# binaryclock.net
KiCad netlist of a schematic drawn in EAGLE
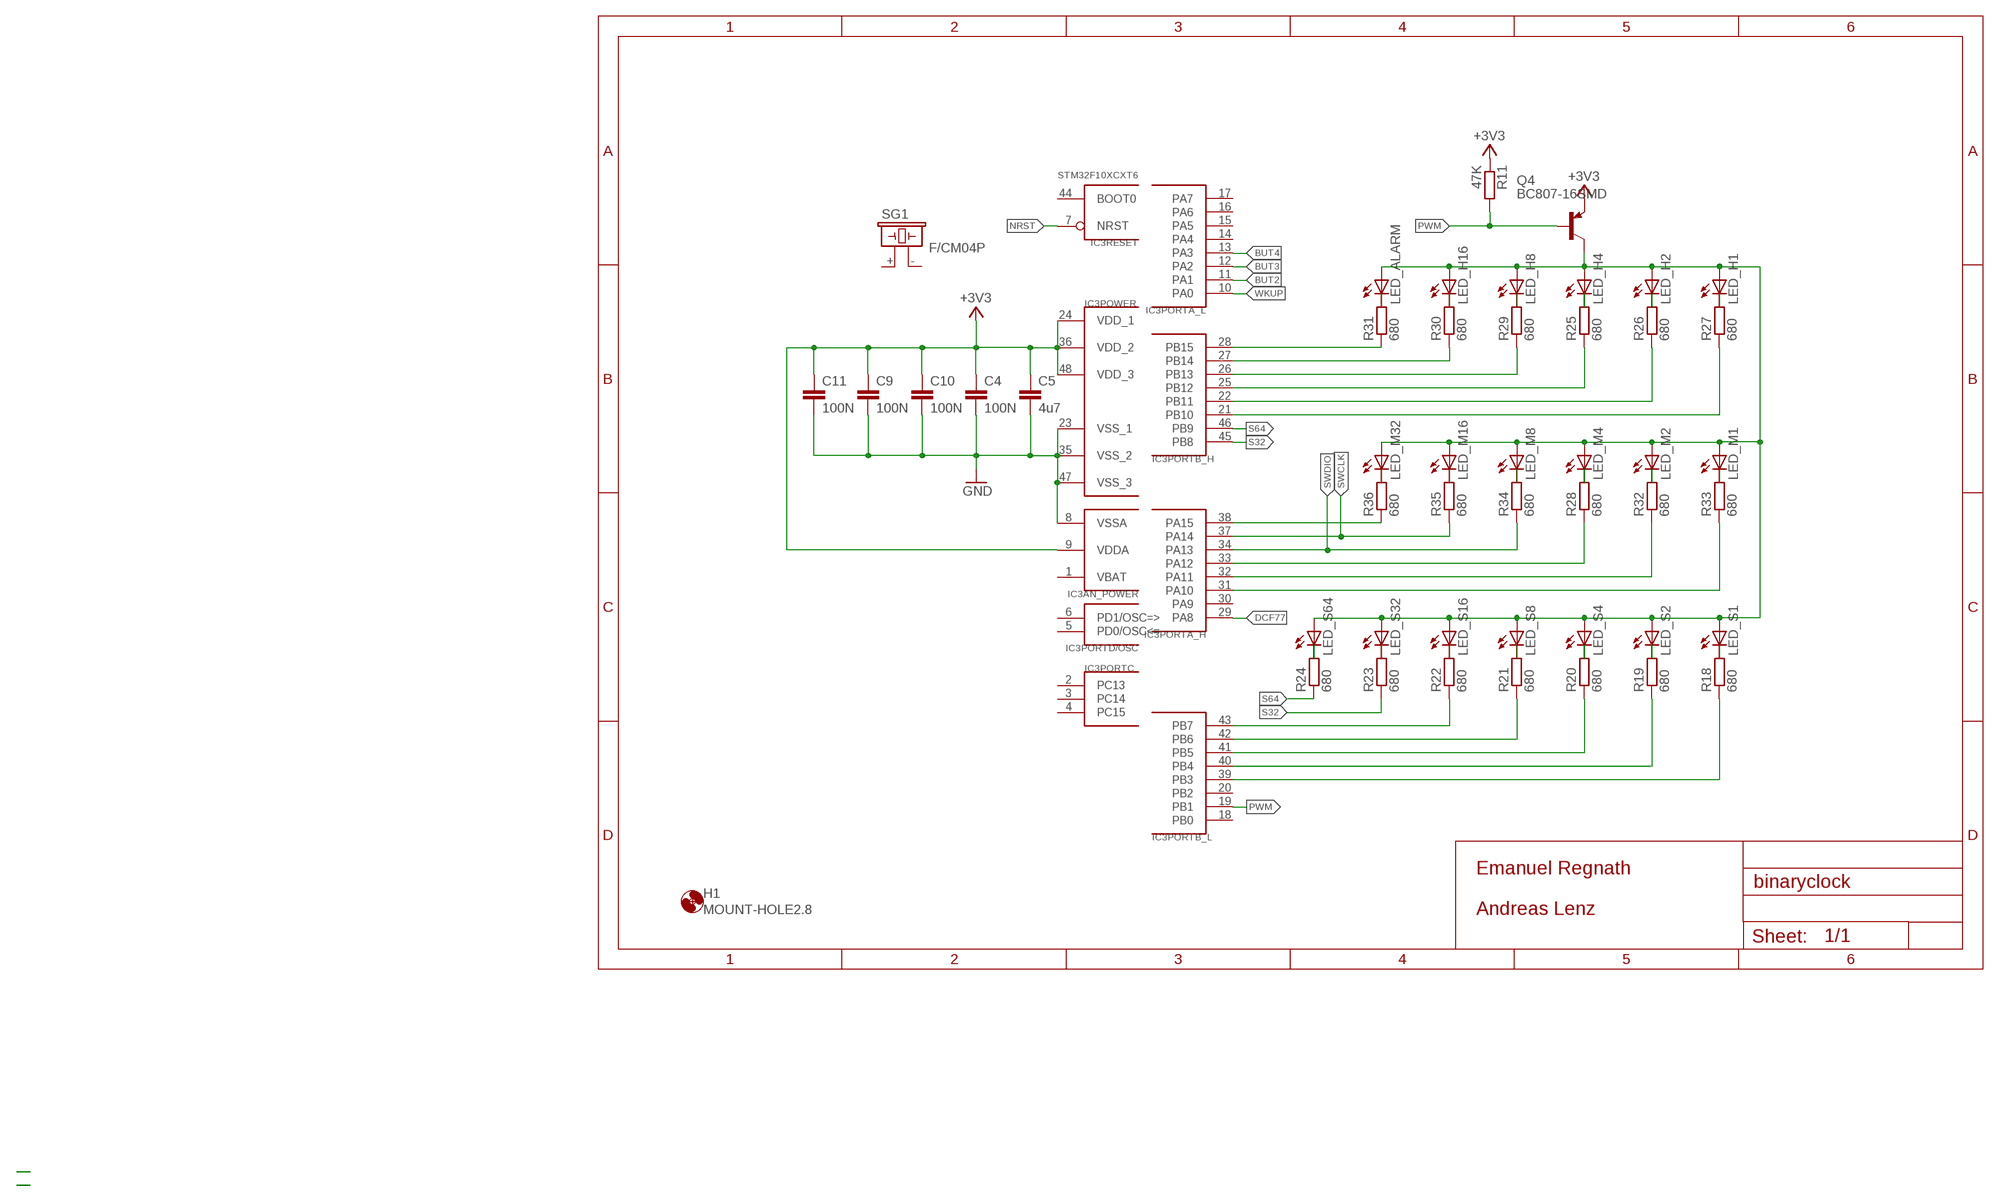
[diagram p0: schematic, sheet 1, part 1 of 2]
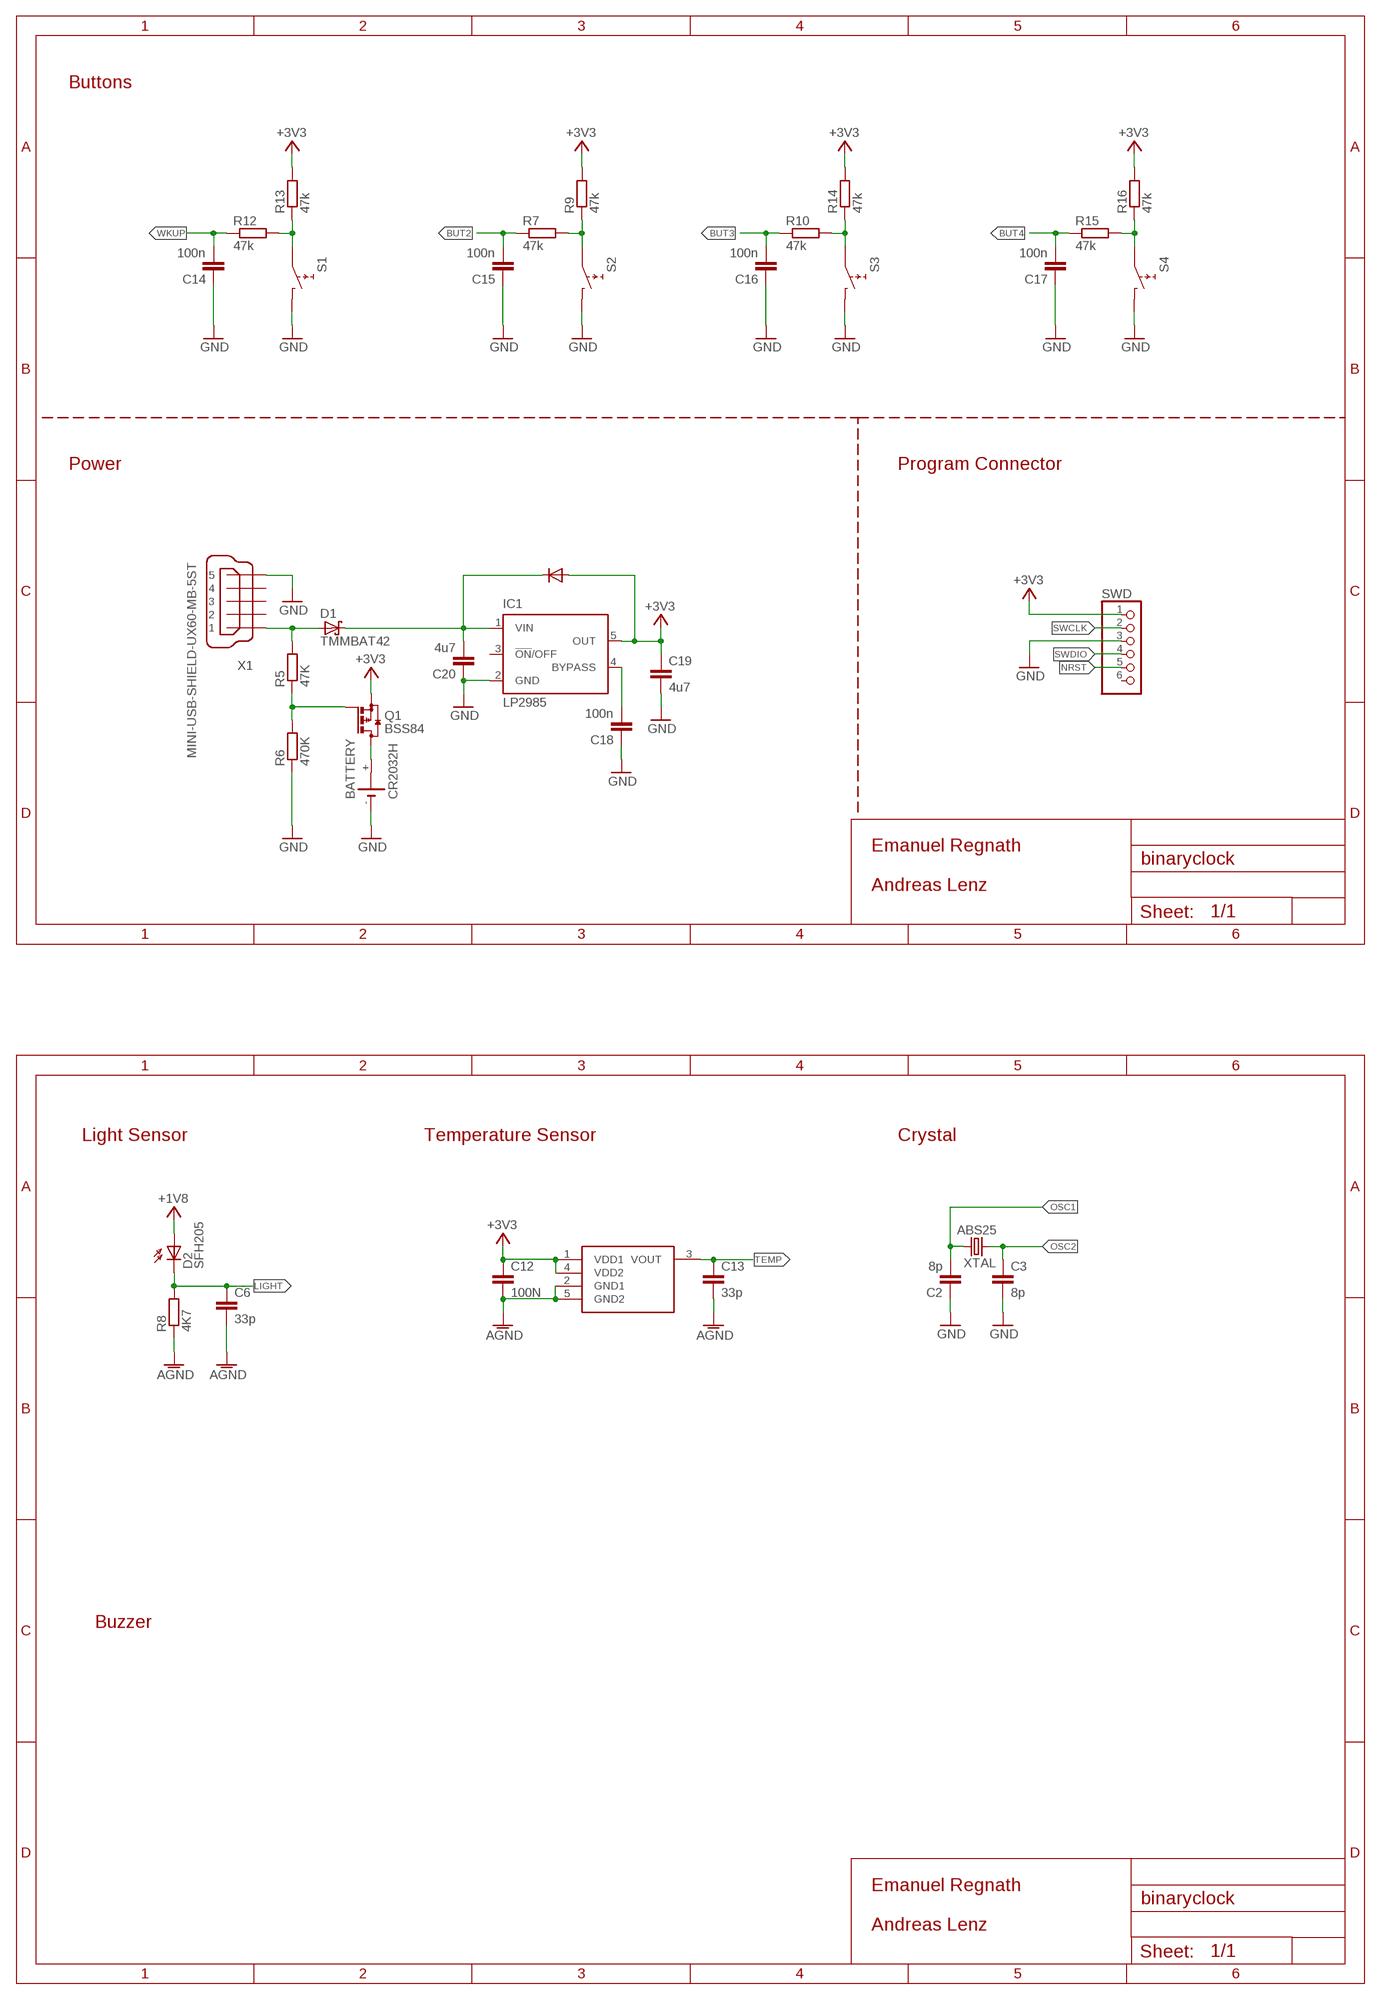
[diagram p1: schematic, sheet 1, part 2 of 2]

(export (version "E")
  (design (tool "Eeschema 10.0.6"))
  (components
    (comp (ref "BATTERY")
      (value "CR2032H")
      (footprint "eagle-import:CR2032H")
      (libsource (lib "eagle-import") (part "CR2032H"))
    )
    (comp (ref "BLA")
      (value "LMT85")
      (footprint "eagle-import:DCK_R-PDSO-G5")
      (libsource (lib "eagle-import") (part "LMT85"))
    )
    (comp (ref "C2")
      (value "8p")
      (footprint "eagle-import:C0805K")
      (libsource (lib "eagle-import") (part "C-EUC0805K"))
    )
    (comp (ref "C3")
      (value "8p")
      (footprint "eagle-import:C0805K")
      (libsource (lib "eagle-import") (part "C-EUC0805K"))
    )
    (comp (ref "C4")
      (value "100N")
      (footprint "eagle-import:C0603")
      (libsource (lib "eagle-import") (part "C-EUC0603"))
    )
    (comp (ref "C5")
      (value "4u7")
      (footprint "eagle-import:C0805")
      (libsource (lib "eagle-import") (part "C-EUC0805"))
    )
    (comp (ref "C6")
      (value "33p")
      (footprint "eagle-import:C0603")
      (libsource (lib "eagle-import") (part "C-EUC0603"))
    )
    (comp (ref "C9")
      (value "100N")
      (footprint "eagle-import:C0603")
      (libsource (lib "eagle-import") (part "C-EUC0603"))
    )
    (comp (ref "C10")
      (value "100N")
      (footprint "eagle-import:C0603")
      (libsource (lib "eagle-import") (part "C-EUC0603"))
    )
    (comp (ref "C11")
      (value "100N")
      (footprint "eagle-import:C0603")
      (libsource (lib "eagle-import") (part "C-EUC0603"))
    )
    (comp (ref "C12")
      (value "100N")
      (footprint "eagle-import:C0603")
      (libsource (lib "eagle-import") (part "C-EUC0603"))
    )
    (comp (ref "C13")
      (value "33p")
      (footprint "eagle-import:C0603")
      (libsource (lib "eagle-import") (part "C-EUC0603"))
    )
    (comp (ref "C14")
      (value "100n")
      (footprint "eagle-import:C0603K")
      (libsource (lib "eagle-import") (part "C-EUC0603K"))
    )
    (comp (ref "C15")
      (value "100n")
      (footprint "eagle-import:C0603K")
      (libsource (lib "eagle-import") (part "C-EUC0603K"))
    )
    (comp (ref "C16")
      (value "100n")
      (footprint "eagle-import:C0603K")
      (libsource (lib "eagle-import") (part "C-EUC0603K"))
    )
    (comp (ref "C17")
      (value "100n")
      (footprint "eagle-import:C0603K")
      (libsource (lib "eagle-import") (part "C-EUC0603K"))
    )
    (comp (ref "C18")
      (value "100n")
      (footprint "eagle-import:C0603K")
      (libsource (lib "eagle-import") (part "C-EUC0603K"))
    )
    (comp (ref "C19")
      (value "4u7")
      (footprint "eagle-import:C0805")
      (libsource (lib "eagle-import") (part "C-EUC0805"))
    )
    (comp (ref "C20")
      (value "4u7")
      (footprint "eagle-import:C0805")
      (libsource (lib "eagle-import") (part "C-EUC0805"))
    )
    (comp (ref "D1")
      (value "TMMBAT42")
      (footprint "eagle-import:SOD80")
      (libsource (lib "eagle-import") (part "TMMBAT42"))
    )
    (comp (ref "D2")
      (value "SFH205")
      (footprint "eagle-import:SFH205")
      (libsource (lib "eagle-import") (part "SFH205"))
    )
    (comp (ref "H1")
      (value "MOUNT-HOLE2.8")
      (footprint "eagle-import:2,8")
      (libsource (lib "eagle-import") (part "MOUNT-HOLE2.8"))
    )
    (comp (ref "IC1")
      (value "LP2985")
      (footprint "eagle-import:SOT23-5")
      (libsource (lib "eagle-import") (part "LP2985"))
    )
    (comp (ref "IC3")
      (value "STM32F10XCXT6")
      (footprint "eagle-import:TQFP48")
      (libsource (lib "eagle-import") (part "STM32F10XCXT6"))
    )
    (comp (ref "LED_ALARM")
      (value "LEDSML0603")
      (footprint "eagle-import:SML0603")
      (libsource (lib "eagle-import") (part "LEDSML0603"))
    )
    (comp (ref "LED_H1")
      (value "LEDSML0603")
      (footprint "eagle-import:SML0603")
      (libsource (lib "eagle-import") (part "LEDSML0603"))
    )
    (comp (ref "LED_H2")
      (value "LEDSML0603")
      (footprint "eagle-import:SML0603")
      (libsource (lib "eagle-import") (part "LEDSML0603"))
    )
    (comp (ref "LED_H4")
      (value "LEDSML0603")
      (footprint "eagle-import:SML0603")
      (libsource (lib "eagle-import") (part "LEDSML0603"))
    )
    (comp (ref "LED_H8")
      (value "LEDSML0603")
      (footprint "eagle-import:SML0603")
      (libsource (lib "eagle-import") (part "LEDSML0603"))
    )
    (comp (ref "LED_H16")
      (value "LEDSML0603")
      (footprint "eagle-import:SML0603")
      (libsource (lib "eagle-import") (part "LEDSML0603"))
    )
    (comp (ref "LED_M1")
      (value "LEDSML0603")
      (footprint "eagle-import:SML0603")
      (libsource (lib "eagle-import") (part "LEDSML0603"))
    )
    (comp (ref "LED_M2")
      (value "LEDSML0603")
      (footprint "eagle-import:SML0603")
      (libsource (lib "eagle-import") (part "LEDSML0603"))
    )
    (comp (ref "LED_M4")
      (value "LEDSML0603")
      (footprint "eagle-import:SML0603")
      (libsource (lib "eagle-import") (part "LEDSML0603"))
    )
    (comp (ref "LED_M8")
      (value "LEDSML0603")
      (footprint "eagle-import:SML0603")
      (libsource (lib "eagle-import") (part "LEDSML0603"))
    )
    (comp (ref "LED_M16")
      (value "LEDSML0603")
      (footprint "eagle-import:SML0603")
      (libsource (lib "eagle-import") (part "LEDSML0603"))
    )
    (comp (ref "LED_M32")
      (value "LEDSML0603")
      (footprint "eagle-import:SML0603")
      (libsource (lib "eagle-import") (part "LEDSML0603"))
    )
    (comp (ref "LED_S1")
      (value "LEDSML0603")
      (footprint "eagle-import:SML0603")
      (libsource (lib "eagle-import") (part "LEDSML0603"))
    )
    (comp (ref "LED_S2")
      (value "LEDSML0603")
      (footprint "eagle-import:SML0603")
      (libsource (lib "eagle-import") (part "LEDSML0603"))
    )
    (comp (ref "LED_S4")
      (value "LEDSML0603")
      (footprint "eagle-import:SML0603")
      (libsource (lib "eagle-import") (part "LEDSML0603"))
    )
    (comp (ref "LED_S8")
      (value "LEDSML0603")
      (footprint "eagle-import:SML0603")
      (libsource (lib "eagle-import") (part "LEDSML0603"))
    )
    (comp (ref "LED_S16")
      (value "LEDSML0603")
      (footprint "eagle-import:SML0603")
      (libsource (lib "eagle-import") (part "LEDSML0603"))
    )
    (comp (ref "LED_S32")
      (value "LEDSML0603")
      (footprint "eagle-import:SML0603")
      (libsource (lib "eagle-import") (part "LEDSML0603"))
    )
    (comp (ref "LED_S64")
      (value "LEDSML0603")
      (footprint "eagle-import:SML0603")
      (libsource (lib "eagle-import") (part "LEDSML0603"))
    )
    (comp (ref "Q1")
      (value "BSS84")
      (footprint "eagle-import:SOT23")
      (libsource (lib "eagle-import") (part "BSS84"))
    )
    (comp (ref "Q4")
      (value "BC807-16SMD")
      (footprint "eagle-import:SOT23-BEC")
      (libsource (lib "eagle-import") (part "BC807SMD-16"))
    )
    (comp (ref "R5")
      (value "47K")
      (footprint "eagle-import:R0805")
      (libsource (lib "eagle-import") (part "resistor_R-EU_R0805"))
    )
    (comp (ref "R6")
      (value "470K")
      (footprint "eagle-import:R0805")
      (libsource (lib "eagle-import") (part "resistor_R-EU_R0805"))
    )
    (comp (ref "R7")
      (value "47k")
      (footprint "eagle-import:M2012")
      (libsource (lib "eagle-import") (part "R-EU_M2012"))
    )
    (comp (ref "R8")
      (value "4K7")
      (footprint "eagle-import:R0603")
      (libsource (lib "eagle-import") (part "resistor_R-EU_R0603"))
    )
    (comp (ref "R9")
      (value "47k")
      (footprint "eagle-import:M2012")
      (libsource (lib "eagle-import") (part "R-EU_M2012"))
    )
    (comp (ref "R10")
      (value "47k")
      (footprint "eagle-import:M2012")
      (libsource (lib "eagle-import") (part "R-EU_M2012"))
    )
    (comp (ref "R11")
      (value "47K")
      (footprint "eagle-import:R0805")
      (libsource (lib "eagle-import") (part "resistor_R-EU_R0805"))
    )
    (comp (ref "R12")
      (value "47k")
      (footprint "eagle-import:M2012")
      (libsource (lib "eagle-import") (part "R-EU_M2012"))
    )
    (comp (ref "R13")
      (value "47k")
      (footprint "eagle-import:M2012")
      (libsource (lib "eagle-import") (part "R-EU_M2012"))
    )
    (comp (ref "R14")
      (value "47k")
      (footprint "eagle-import:M2012")
      (libsource (lib "eagle-import") (part "R-EU_M2012"))
    )
    (comp (ref "R15")
      (value "47k")
      (footprint "eagle-import:M2012")
      (libsource (lib "eagle-import") (part "R-EU_M2012"))
    )
    (comp (ref "R16")
      (value "47k")
      (footprint "eagle-import:M2012")
      (libsource (lib "eagle-import") (part "R-EU_M2012"))
    )
    (comp (ref "R18")
      (value "680")
      (footprint "eagle-import:R0603")
      (libsource (lib "eagle-import") (part "resistor_R-EU_R0603"))
    )
    (comp (ref "R19")
      (value "680")
      (footprint "eagle-import:R0603")
      (libsource (lib "eagle-import") (part "resistor_R-EU_R0603"))
    )
    (comp (ref "R20")
      (value "680")
      (footprint "eagle-import:R0603")
      (libsource (lib "eagle-import") (part "resistor_R-EU_R0603"))
    )
    (comp (ref "R21")
      (value "680")
      (footprint "eagle-import:R0603")
      (libsource (lib "eagle-import") (part "resistor_R-EU_R0603"))
    )
    (comp (ref "R22")
      (value "680")
      (footprint "eagle-import:R0603")
      (libsource (lib "eagle-import") (part "resistor_R-EU_R0603"))
    )
    (comp (ref "R23")
      (value "680")
      (footprint "eagle-import:R0603")
      (libsource (lib "eagle-import") (part "resistor_R-EU_R0603"))
    )
    (comp (ref "R24")
      (value "680")
      (footprint "eagle-import:R0603")
      (libsource (lib "eagle-import") (part "resistor_R-EU_R0603"))
    )
    (comp (ref "R25")
      (value "680")
      (footprint "eagle-import:R0603")
      (libsource (lib "eagle-import") (part "resistor_R-EU_R0603"))
    )
    (comp (ref "R26")
      (value "680")
      (footprint "eagle-import:R0603")
      (libsource (lib "eagle-import") (part "resistor_R-EU_R0603"))
    )
    (comp (ref "R27")
      (value "680")
      (footprint "eagle-import:R0603")
      (libsource (lib "eagle-import") (part "resistor_R-EU_R0603"))
    )
    (comp (ref "R28")
      (value "680")
      (footprint "eagle-import:R0603")
      (libsource (lib "eagle-import") (part "resistor_R-EU_R0603"))
    )
    (comp (ref "R29")
      (value "680")
      (footprint "eagle-import:R0603")
      (libsource (lib "eagle-import") (part "resistor_R-EU_R0603"))
    )
    (comp (ref "R30")
      (value "680")
      (footprint "eagle-import:R0603")
      (libsource (lib "eagle-import") (part "resistor_R-EU_R0603"))
    )
    (comp (ref "R31")
      (value "680")
      (footprint "eagle-import:R0603")
      (libsource (lib "eagle-import") (part "resistor_R-EU_R0603"))
    )
    (comp (ref "R32")
      (value "680")
      (footprint "eagle-import:R0603")
      (libsource (lib "eagle-import") (part "resistor_R-EU_R0603"))
    )
    (comp (ref "R33")
      (value "680")
      (footprint "eagle-import:R0603")
      (libsource (lib "eagle-import") (part "resistor_R-EU_R0603"))
    )
    (comp (ref "R34")
      (value "680")
      (footprint "eagle-import:R0603")
      (libsource (lib "eagle-import") (part "resistor_R-EU_R0603"))
    )
    (comp (ref "R35")
      (value "680")
      (footprint "eagle-import:R0603")
      (libsource (lib "eagle-import") (part "resistor_R-EU_R0603"))
    )
    (comp (ref "R36")
      (value "680")
      (footprint "eagle-import:R0603")
      (libsource (lib "eagle-import") (part "resistor_R-EU_R0603"))
    )
    (comp (ref "S1")
      (value "SWITCH1")
      (footprint "eagle-import:SWITCH1")
      (libsource (lib "eagle-import") (part "SWITCH1"))
    )
    (comp (ref "S2")
      (value "SWITCH1")
      (footprint "eagle-import:SWITCH1")
      (libsource (lib "eagle-import") (part "SWITCH1"))
    )
    (comp (ref "S3")
      (value "SWITCH1")
      (footprint "eagle-import:SWITCH1")
      (libsource (lib "eagle-import") (part "SWITCH1"))
    )
    (comp (ref "S4")
      (value "SWITCH1")
      (footprint "eagle-import:SWITCH1")
      (libsource (lib "eagle-import") (part "SWITCH1"))
    )
    (comp (ref "SG1")
      (value "F/CM04P")
      (footprint "eagle-import:F_CM04P")
      (libsource (lib "eagle-import") (part "F/CM04P"))
    )
    (comp (ref "SWD")
      (value "PINHD-1X6")
      (footprint "eagle-import:1X06")
      (libsource (lib "eagle-import") (part "PINHD-1X6"))
    )
    (comp (ref "X1")
      (value "MINI-USB-SHIELD-UX60-MB-5ST")
      (footprint "eagle-import:UX60-MB-5ST")
      (libsource (lib "eagle-import") (part "MINI-USB-SHIELD-UX60-MB-5ST"))
    )
    (comp (ref "XTAL")
      (value "ABS25")
      (footprint "eagle-import:ABS25")
      (fields (field (name "MPN") "MC-306 60.0KHZ  100PPM ,12.5PF"))
      (libsource (lib "eagle-import") (part "ABS25"))
    )
  )
  (nets
    (net (code "1") (name "+1V8") (class "Default")
      (node (ref "D2") (pin "A") (pinfunction "A_A") (pintype "passive"))
    )
    (net (code "2") (name "+3V3") (class "Default")
      (node (ref "BLA") (pin "1") (pinfunction "VDD1_1") (pintype "power_in"))
      (node (ref "BLA") (pin "4") (pinfunction "VDD2_4") (pintype "power_in"))
      (node (ref "C10") (pin "1") (pinfunction "1_1") (pintype "passive"))
      (node (ref "C11") (pin "1") (pinfunction "1_1") (pintype "passive"))
      (node (ref "C12") (pin "1") (pinfunction "1_1") (pintype "passive"))
      (node (ref "C19") (pin "1") (pinfunction "1_1") (pintype "passive"))
      (node (ref "C4") (pin "1") (pinfunction "1_1") (pintype "passive"))
      (node (ref "C5") (pin "1") (pinfunction "1_1") (pintype "passive"))
      (node (ref "C9") (pin "1") (pinfunction "1_1") (pintype "passive"))
      (node (ref "IC1") (pin "5") (pinfunction "OUT_5") (pintype "output"))
      (node (ref "IC3") (pin "24") (pinfunction "VDD_1_24") (pintype "power_in"))
      (node (ref "IC3") (pin "36") (pinfunction "VDD_2_36") (pintype "power_in"))
      (node (ref "IC3") (pin "48") (pinfunction "VDD_3_48") (pintype "power_in"))
      (node (ref "IC3") (pin "9") (pinfunction "VDDA_9") (pintype "power_in"))
      (node (ref "Q1") (pin "2") (pinfunction "S_2") (pintype "passive"))
      (node (ref "Q4") (pin "E") (pinfunction "E_E") (pintype "passive"))
      (node (ref "R11") (pin "1") (pinfunction "1_1") (pintype "passive"))
      (node (ref "R13") (pin "2") (pinfunction "2_2") (pintype "passive"))
      (node (ref "R14") (pin "2") (pinfunction "2_2") (pintype "passive"))
      (node (ref "R16") (pin "2") (pinfunction "2_2") (pintype "passive"))
      (node (ref "R9") (pin "2") (pinfunction "2_2") (pintype "passive"))
      (node (ref "SWD") (pin "1") (pinfunction "1_1") (pintype "passive"))
    )
    (net (code "3") (name "/VBAT") (class "Default")
      (node (ref "IC3") (pin "1") (pinfunction "VBAT_1") (pintype "power_in"))
    )
    (net (code "4") (name "AGND") (class "Default")
      (node (ref "BLA") (pin "2") (pinfunction "GND1_2") (pintype "power_in"))
      (node (ref "BLA") (pin "5") (pinfunction "GND2_5") (pintype "power_in"))
      (node (ref "C12") (pin "2") (pinfunction "2_2") (pintype "passive"))
      (node (ref "C13") (pin "2") (pinfunction "2_2") (pintype "passive"))
      (node (ref "C6") (pin "2") (pinfunction "2_2") (pintype "passive"))
      (node (ref "R8") (pin "1") (pinfunction "1_1") (pintype "passive"))
    )
    (net (code "5") (name "BUT2") (class "Default")
      (node (ref "C15") (pin "2") (pinfunction "2_2") (pintype "passive"))
      (node (ref "IC3") (pin "11") (pinfunction "PA1_11") (pintype "bidirectional"))
      (node (ref "R7") (pin "1") (pinfunction "1_1") (pintype "passive"))
    )
    (net (code "6") (name "BUT3") (class "Default")
      (node (ref "C16") (pin "2") (pinfunction "2_2") (pintype "passive"))
      (node (ref "IC3") (pin "12") (pinfunction "PA2_12") (pintype "bidirectional"))
      (node (ref "R10") (pin "1") (pinfunction "1_1") (pintype "passive"))
    )
    (net (code "7") (name "BUT4") (class "Default")
      (node (ref "C17") (pin "2") (pinfunction "2_2") (pintype "passive"))
      (node (ref "IC3") (pin "13") (pinfunction "PA3_13") (pintype "bidirectional"))
      (node (ref "R15") (pin "1") (pinfunction "1_1") (pintype "passive"))
    )
    (net (code "8") (name "DCF77") (class "Default")
      (node (ref "IC3") (pin "29") (pinfunction "PA8_29") (pintype "bidirectional"))
    )
    (net (code "9") (name "GND") (class "Default")
      (node (ref "BATTERY") (pin "-") (pinfunction "-_-") (pintype "passive"))
      (node (ref "C10") (pin "2") (pinfunction "2_2") (pintype "passive"))
      (node (ref "C11") (pin "2") (pinfunction "2_2") (pintype "passive"))
      (node (ref "C14") (pin "1") (pinfunction "1_1") (pintype "passive"))
      (node (ref "C15") (pin "1") (pinfunction "1_1") (pintype "passive"))
      (node (ref "C16") (pin "1") (pinfunction "1_1") (pintype "passive"))
      (node (ref "C17") (pin "1") (pinfunction "1_1") (pintype "passive"))
      (node (ref "C18") (pin "1") (pinfunction "1_1") (pintype "passive"))
      (node (ref "C19") (pin "2") (pinfunction "2_2") (pintype "passive"))
      (node (ref "C2") (pin "1") (pinfunction "1_1") (pintype "passive"))
      (node (ref "C20") (pin "1") (pinfunction "1_1") (pintype "passive"))
      (node (ref "C3") (pin "2") (pinfunction "2_2") (pintype "passive"))
      (node (ref "C4") (pin "2") (pinfunction "2_2") (pintype "passive"))
      (node (ref "C5") (pin "2") (pinfunction "2_2") (pintype "passive"))
      (node (ref "C9") (pin "2") (pinfunction "2_2") (pintype "passive"))
      (node (ref "IC1") (pin "2") (pinfunction "GND_2") (pintype "power_in"))
      (node (ref "IC3") (pin "23") (pinfunction "VSS_1_23") (pintype "power_in"))
      (node (ref "IC3") (pin "35") (pinfunction "VSS_2_35") (pintype "power_in"))
      (node (ref "IC3") (pin "47") (pinfunction "VSS_3_47") (pintype "power_in"))
      (node (ref "IC3") (pin "8") (pinfunction "VSSA_8") (pintype "power_in"))
      (node (ref "R6") (pin "1") (pinfunction "1_1") (pintype "passive"))
      (node (ref "S1") (pin "P$2") (pinfunction "1_P$2") (pintype "passive"))
      (node (ref "S2") (pin "P$2") (pinfunction "1_P$2") (pintype "passive"))
      (node (ref "S3") (pin "P$2") (pinfunction "1_P$2") (pintype "passive"))
      (node (ref "S4") (pin "P$2") (pinfunction "1_P$2") (pintype "passive"))
      (node (ref "SWD") (pin "3") (pinfunction "3_3") (pintype "passive"))
      (node (ref "X1") (pin "5") (pinfunction "5_5") (pintype "input"))
    )
    (net (code "10") (name "LIGHT") (class "Default")
      (node (ref "C6") (pin "1") (pinfunction "1_1") (pintype "passive"))
      (node (ref "D2") (pin "K") (pinfunction "C_K") (pintype "passive"))
      (node (ref "R8") (pin "2") (pinfunction "2_2") (pintype "passive"))
    )
    (net (code "11") (name "NRST") (class "Default")
      (node (ref "IC3") (pin "7") (pinfunction "NRST_7") (pintype "input"))
      (node (ref "SWD") (pin "5") (pinfunction "5_5") (pintype "passive"))
    )
    (net (code "12") (name "Net-(D1-A)") (class "Default")
      (node (ref "D1") (pin "2") (pinfunction "A_2") (pintype "passive"))
      (node (ref "R5") (pin "2") (pinfunction "2_2") (pintype "passive"))
      (node (ref "X1") (pin "1") (pinfunction "1_1") (pintype "input"))
    )
    (net (code "13") (name "Net-(D1-C)") (class "Default")
      (node (ref "C20") (pin "2") (pinfunction "2_2") (pintype "passive"))
      (node (ref "D1") (pin "1") (pinfunction "C_1") (pintype "passive"))
      (node (ref "IC1") (pin "1") (pinfunction "VIN_1") (pintype "input"))
    )
    (net (code "14") (name "Net-(IC1-BYPASS)") (class "Default")
      (node (ref "C18") (pin "2") (pinfunction "2_2") (pintype "passive"))
      (node (ref "IC1") (pin "4") (pinfunction "BYPASS_4") (pintype "passive"))
    )
    (net (code "15") (name "Net-(IC3B-PA10)") (class "Default")
      (node (ref "IC3") (pin "31") (pinfunction "PA10_31") (pintype "bidirectional"))
      (node (ref "R33") (pin "1") (pinfunction "1_1") (pintype "passive"))
    )
    (net (code "16") (name "Net-(IC3B-PA11)") (class "Default")
      (node (ref "IC3") (pin "32") (pinfunction "PA11_32") (pintype "bidirectional"))
      (node (ref "R32") (pin "1") (pinfunction "1_1") (pintype "passive"))
    )
    (net (code "17") (name "Net-(IC3B-PA12)") (class "Default")
      (node (ref "IC3") (pin "33") (pinfunction "PA12_33") (pintype "bidirectional"))
      (node (ref "R28") (pin "1") (pinfunction "1_1") (pintype "passive"))
    )
    (net (code "18") (name "Net-(IC3B-PA15)") (class "Default")
      (node (ref "IC3") (pin "38") (pinfunction "PA15_38") (pintype "bidirectional"))
      (node (ref "R36") (pin "1") (pinfunction "1_1") (pintype "passive"))
    )
    (net (code "19") (name "Net-(IC3D-PB10)") (class "Default")
      (node (ref "IC3") (pin "21") (pinfunction "PB10_21") (pintype "bidirectional"))
      (node (ref "R27") (pin "1") (pinfunction "1_1") (pintype "passive"))
    )
    (net (code "20") (name "Net-(IC3D-PB11)") (class "Default")
      (node (ref "IC3") (pin "22") (pinfunction "PB11_22") (pintype "bidirectional"))
      (node (ref "R26") (pin "1") (pinfunction "1_1") (pintype "passive"))
    )
    (net (code "21") (name "Net-(IC3D-PB12)") (class "Default")
      (node (ref "IC3") (pin "25") (pinfunction "PB12_25") (pintype "bidirectional"))
      (node (ref "R25") (pin "1") (pinfunction "1_1") (pintype "passive"))
    )
    (net (code "22") (name "Net-(IC3D-PB13)") (class "Default")
      (node (ref "IC3") (pin "26") (pinfunction "PB13_26") (pintype "bidirectional"))
      (node (ref "R29") (pin "1") (pinfunction "1_1") (pintype "passive"))
    )
    (net (code "23") (name "Net-(IC3D-PB14)") (class "Default")
      (node (ref "IC3") (pin "27") (pinfunction "PB14_27") (pintype "bidirectional"))
      (node (ref "R30") (pin "1") (pinfunction "1_1") (pintype "passive"))
    )
    (net (code "24") (name "Net-(IC3D-PB15)") (class "Default")
      (node (ref "IC3") (pin "28") (pinfunction "PB15_28") (pintype "bidirectional"))
      (node (ref "R31") (pin "1") (pinfunction "1_1") (pintype "passive"))
    )
    (net (code "25") (name "Net-(IC3E-PB3)") (class "Default")
      (node (ref "IC3") (pin "39") (pinfunction "PB3_39") (pintype "bidirectional"))
      (node (ref "R18") (pin "1") (pinfunction "1_1") (pintype "passive"))
    )
    (net (code "26") (name "Net-(IC3E-PB4)") (class "Default")
      (node (ref "IC3") (pin "40") (pinfunction "PB4_40") (pintype "bidirectional"))
      (node (ref "R19") (pin "1") (pinfunction "1_1") (pintype "passive"))
    )
    (net (code "27") (name "Net-(IC3E-PB5)") (class "Default")
      (node (ref "IC3") (pin "41") (pinfunction "PB5_41") (pintype "bidirectional"))
      (node (ref "R20") (pin "1") (pinfunction "1_1") (pintype "passive"))
    )
    (net (code "28") (name "Net-(IC3E-PB6)") (class "Default")
      (node (ref "IC3") (pin "42") (pinfunction "PB6_42") (pintype "bidirectional"))
      (node (ref "R21") (pin "1") (pinfunction "1_1") (pintype "passive"))
    )
    (net (code "29") (name "Net-(IC3E-PB7)") (class "Default")
      (node (ref "IC3") (pin "43") (pinfunction "PB7_43") (pintype "bidirectional"))
      (node (ref "R22") (pin "1") (pinfunction "1_1") (pintype "passive"))
    )
    (net (code "30") (name "Net-(LED_ALARM-PadA)") (class "Default")
      (node (ref "LED_ALARM") (pin "A") (pinfunction "A_A") (pintype "passive"))
      (node (ref "LED_H1") (pin "A") (pinfunction "A_A") (pintype "passive"))
      (node (ref "LED_H16") (pin "A") (pinfunction "A_A") (pintype "passive"))
      (node (ref "LED_H2") (pin "A") (pinfunction "A_A") (pintype "passive"))
      (node (ref "LED_H4") (pin "A") (pinfunction "A_A") (pintype "passive"))
      (node (ref "LED_H8") (pin "A") (pinfunction "A_A") (pintype "passive"))
      (node (ref "LED_M1") (pin "A") (pinfunction "A_A") (pintype "passive"))
      (node (ref "LED_M16") (pin "A") (pinfunction "A_A") (pintype "passive"))
      (node (ref "LED_M2") (pin "A") (pinfunction "A_A") (pintype "passive"))
      (node (ref "LED_M32") (pin "A") (pinfunction "A_A") (pintype "passive"))
      (node (ref "LED_M4") (pin "A") (pinfunction "A_A") (pintype "passive"))
      (node (ref "LED_M8") (pin "A") (pinfunction "A_A") (pintype "passive"))
      (node (ref "LED_S1") (pin "A") (pinfunction "A_A") (pintype "passive"))
      (node (ref "LED_S16") (pin "A") (pinfunction "A_A") (pintype "passive"))
      (node (ref "LED_S2") (pin "A") (pinfunction "A_A") (pintype "passive"))
      (node (ref "LED_S32") (pin "A") (pinfunction "A_A") (pintype "passive"))
      (node (ref "LED_S4") (pin "A") (pinfunction "A_A") (pintype "passive"))
      (node (ref "LED_S64") (pin "A") (pinfunction "A_A") (pintype "passive"))
      (node (ref "LED_S8") (pin "A") (pinfunction "A_A") (pintype "passive"))
      (node (ref "Q4") (pin "C") (pinfunction "C_C") (pintype "passive"))
    )
    (net (code "31") (name "Net-(LED_ALARM-PadC)") (class "Default")
      (node (ref "LED_ALARM") (pin "C") (pinfunction "C_C") (pintype "passive"))
      (node (ref "R31") (pin "2") (pinfunction "2_2") (pintype "passive"))
    )
    (net (code "32") (name "Net-(LED_H1-PadC)") (class "Default")
      (node (ref "LED_H1") (pin "C") (pinfunction "C_C") (pintype "passive"))
      (node (ref "R27") (pin "2") (pinfunction "2_2") (pintype "passive"))
    )
    (net (code "33") (name "Net-(LED_H2-PadC)") (class "Default")
      (node (ref "LED_H2") (pin "C") (pinfunction "C_C") (pintype "passive"))
      (node (ref "R26") (pin "2") (pinfunction "2_2") (pintype "passive"))
    )
    (net (code "34") (name "Net-(LED_H4-PadC)") (class "Default")
      (node (ref "LED_H4") (pin "C") (pinfunction "C_C") (pintype "passive"))
      (node (ref "R25") (pin "2") (pinfunction "2_2") (pintype "passive"))
    )
    (net (code "35") (name "Net-(LED_H8-PadC)") (class "Default")
      (node (ref "LED_H8") (pin "C") (pinfunction "C_C") (pintype "passive"))
      (node (ref "R29") (pin "2") (pinfunction "2_2") (pintype "passive"))
    )
    (net (code "36") (name "Net-(LED_H16-PadC)") (class "Default")
      (node (ref "LED_H16") (pin "C") (pinfunction "C_C") (pintype "passive"))
      (node (ref "R30") (pin "2") (pinfunction "2_2") (pintype "passive"))
    )
    (net (code "37") (name "Net-(LED_M1-PadC)") (class "Default")
      (node (ref "LED_M1") (pin "C") (pinfunction "C_C") (pintype "passive"))
      (node (ref "R33") (pin "2") (pinfunction "2_2") (pintype "passive"))
    )
    (net (code "38") (name "Net-(LED_M2-PadC)") (class "Default")
      (node (ref "LED_M2") (pin "C") (pinfunction "C_C") (pintype "passive"))
      (node (ref "R32") (pin "2") (pinfunction "2_2") (pintype "passive"))
    )
    (net (code "39") (name "Net-(LED_M4-PadC)") (class "Default")
      (node (ref "LED_M4") (pin "C") (pinfunction "C_C") (pintype "passive"))
      (node (ref "R28") (pin "2") (pinfunction "2_2") (pintype "passive"))
    )
    (net (code "40") (name "Net-(LED_M8-PadC)") (class "Default")
      (node (ref "LED_M8") (pin "C") (pinfunction "C_C") (pintype "passive"))
      (node (ref "R34") (pin "2") (pinfunction "2_2") (pintype "passive"))
    )
    (net (code "41") (name "Net-(LED_M16-PadC)") (class "Default")
      (node (ref "LED_M16") (pin "C") (pinfunction "C_C") (pintype "passive"))
      (node (ref "R35") (pin "2") (pinfunction "2_2") (pintype "passive"))
    )
    (net (code "42") (name "Net-(LED_M32-PadC)") (class "Default")
      (node (ref "LED_M32") (pin "C") (pinfunction "C_C") (pintype "passive"))
      (node (ref "R36") (pin "2") (pinfunction "2_2") (pintype "passive"))
    )
    (net (code "43") (name "Net-(LED_S1-PadC)") (class "Default")
      (node (ref "LED_S1") (pin "C") (pinfunction "C_C") (pintype "passive"))
      (node (ref "R18") (pin "2") (pinfunction "2_2") (pintype "passive"))
    )
    (net (code "44") (name "Net-(LED_S2-PadC)") (class "Default")
      (node (ref "LED_S2") (pin "C") (pinfunction "C_C") (pintype "passive"))
      (node (ref "R19") (pin "2") (pinfunction "2_2") (pintype "passive"))
    )
    (net (code "45") (name "Net-(LED_S4-PadC)") (class "Default")
      (node (ref "LED_S4") (pin "C") (pinfunction "C_C") (pintype "passive"))
      (node (ref "R20") (pin "2") (pinfunction "2_2") (pintype "passive"))
    )
    (net (code "46") (name "Net-(LED_S8-PadC)") (class "Default")
      (node (ref "LED_S8") (pin "C") (pinfunction "C_C") (pintype "passive"))
      (node (ref "R21") (pin "2") (pinfunction "2_2") (pintype "passive"))
    )
    (net (code "47") (name "Net-(LED_S16-PadC)") (class "Default")
      (node (ref "LED_S16") (pin "C") (pinfunction "C_C") (pintype "passive"))
      (node (ref "R22") (pin "2") (pinfunction "2_2") (pintype "passive"))
    )
    (net (code "48") (name "Net-(LED_S32-PadC)") (class "Default")
      (node (ref "LED_S32") (pin "C") (pinfunction "C_C") (pintype "passive"))
      (node (ref "R23") (pin "2") (pinfunction "2_2") (pintype "passive"))
    )
    (net (code "49") (name "Net-(LED_S64-PadC)") (class "Default")
      (node (ref "LED_S64") (pin "C") (pinfunction "C_C") (pintype "passive"))
      (node (ref "R24") (pin "2") (pinfunction "2_2") (pintype "passive"))
    )
    (net (code "50") (name "Net-(Q1-D)") (class "Default")
      (node (ref "BATTERY") (pin "+") (pinfunction "+_+") (pintype "passive"))
      (node (ref "Q1") (pin "3") (pinfunction "D_3") (pintype "passive"))
    )
    (net (code "51") (name "Net-(Q1-G)") (class "Default")
      (node (ref "Q1") (pin "1") (pinfunction "G_1") (pintype "passive"))
      (node (ref "R5") (pin "1") (pinfunction "1_1") (pintype "passive"))
      (node (ref "R6") (pin "2") (pinfunction "2_2") (pintype "passive"))
    )
    (net (code "52") (name "Net-(S1-0)") (class "Default")
      (node (ref "R12") (pin "2") (pinfunction "2_2") (pintype "passive"))
      (node (ref "R13") (pin "1") (pinfunction "1_1") (pintype "passive"))
      (node (ref "S1") (pin "P$1") (pinfunction "0_P$1") (pintype "passive"))
    )
    (net (code "53") (name "Net-(S2-0)") (class "Default")
      (node (ref "R7") (pin "2") (pinfunction "2_2") (pintype "passive"))
      (node (ref "R9") (pin "1") (pinfunction "1_1") (pintype "passive"))
      (node (ref "S2") (pin "P$1") (pinfunction "0_P$1") (pintype "passive"))
    )
    (net (code "54") (name "Net-(S3-0)") (class "Default")
      (node (ref "R10") (pin "2") (pinfunction "2_2") (pintype "passive"))
      (node (ref "R14") (pin "1") (pinfunction "1_1") (pintype "passive"))
      (node (ref "S3") (pin "P$1") (pinfunction "0_P$1") (pintype "passive"))
    )
    (net (code "55") (name "Net-(S4-0)") (class "Default")
      (node (ref "R15") (pin "2") (pinfunction "2_2") (pintype "passive"))
      (node (ref "R16") (pin "1") (pinfunction "1_1") (pintype "passive"))
      (node (ref "S4") (pin "P$1") (pinfunction "0_P$1") (pintype "passive"))
    )
    (net (code "56") (name "OSC1") (class "Default")
      (node (ref "C2") (pin "2") (pinfunction "2_2") (pintype "passive"))
      (node (ref "XTAL") (pin "1") (pinfunction "1_1") (pintype "passive"))
    )
    (net (code "57") (name "OSC2") (class "Default")
      (node (ref "C3") (pin "1") (pinfunction "1_1") (pintype "passive"))
      (node (ref "XTAL") (pin "4") (pinfunction "2_4") (pintype "passive"))
    )
    (net (code "58") (name "PWM") (class "Default")
      (node (ref "IC3") (pin "19") (pinfunction "PB1_19") (pintype "bidirectional"))
      (node (ref "Q4") (pin "B") (pinfunction "B_B") (pintype "passive"))
      (node (ref "R11") (pin "2") (pinfunction "2_2") (pintype "passive"))
    )
    (net (code "59") (name "S32") (class "Default")
      (node (ref "IC3") (pin "45") (pinfunction "PB8_45") (pintype "bidirectional"))
      (node (ref "R23") (pin "1") (pinfunction "1_1") (pintype "passive"))
    )
    (net (code "60") (name "S64") (class "Default")
      (node (ref "IC3") (pin "46") (pinfunction "PB9_46") (pintype "bidirectional"))
      (node (ref "R24") (pin "1") (pinfunction "1_1") (pintype "passive"))
    )
    (net (code "61") (name "SWCLK") (class "Default")
      (node (ref "IC3") (pin "37") (pinfunction "PA14_37") (pintype "bidirectional"))
      (node (ref "R35") (pin "1") (pinfunction "1_1") (pintype "passive"))
      (node (ref "SWD") (pin "2") (pinfunction "2_2") (pintype "passive"))
    )
    (net (code "62") (name "SWDIO") (class "Default")
      (node (ref "IC3") (pin "34") (pinfunction "PA13_34") (pintype "bidirectional"))
      (node (ref "R34") (pin "1") (pinfunction "1_1") (pintype "passive"))
      (node (ref "SWD") (pin "4") (pinfunction "4_4") (pintype "passive"))
    )
    (net (code "63") (name "TEMP") (class "Default")
      (node (ref "BLA") (pin "3") (pinfunction "VOUT_3") (pintype "output"))
      (node (ref "C13") (pin "1") (pinfunction "1_1") (pintype "passive"))
    )
    (net (code "64") (name "WKUP") (class "Default")
      (node (ref "C14") (pin "2") (pinfunction "2_2") (pintype "passive"))
      (node (ref "IC3") (pin "10") (pinfunction "PA0_10") (pintype "bidirectional"))
      (node (ref "R12") (pin "1") (pinfunction "1_1") (pintype "passive"))
    )
    (net (code "65") (name "unconnected-(BATTERY-+-Pad+@1)") (class "Default")
      (node (ref "BATTERY") (pin "+@1") (pinfunction "+_+@1") (pintype "passive"))
    )
    (net (code "66") (name "unconnected-(IC1-~{ON}{slash}OFF-Pad3)") (class "Default")
      (node (ref "IC1") (pin "3") (pinfunction "~{ON}/OFF_3") (pintype "input"))
    )
    (net (code "67") (name "unconnected-(IC3B-PA9-Pad30)") (class "Default")
      (node (ref "IC3") (pin "30") (pinfunction "PA9_30") (pintype "bidirectional"))
    )
    (net (code "68") (name "unconnected-(IC3C-PA4-Pad14)") (class "Default")
      (node (ref "IC3") (pin "14") (pinfunction "PA4_14") (pintype "bidirectional"))
    )
    (net (code "69") (name "unconnected-(IC3C-PA5-Pad15)") (class "Default")
      (node (ref "IC3") (pin "15") (pinfunction "PA5_15") (pintype "bidirectional"))
    )
    (net (code "70") (name "unconnected-(IC3C-PA6-Pad16)") (class "Default")
      (node (ref "IC3") (pin "16") (pinfunction "PA6_16") (pintype "bidirectional"))
    )
    (net (code "71") (name "unconnected-(IC3C-PA7-Pad17)") (class "Default")
      (node (ref "IC3") (pin "17") (pinfunction "PA7_17") (pintype "bidirectional"))
    )
    (net (code "72") (name "unconnected-(IC3E-PB0-Pad18)") (class "Default")
      (node (ref "IC3") (pin "18") (pinfunction "PB0_18") (pintype "bidirectional"))
    )
    (net (code "73") (name "unconnected-(IC3E-PB2-Pad20)") (class "Default")
      (node (ref "IC3") (pin "20") (pinfunction "PB2_20") (pintype "bidirectional"))
    )
    (net (code "74") (name "unconnected-(IC3F-PC13-Pad2)") (class "Default")
      (node (ref "IC3") (pin "2") (pinfunction "PC13_2") (pintype "bidirectional"))
    )
    (net (code "75") (name "unconnected-(IC3F-PC14-Pad3)") (class "Default")
      (node (ref "IC3") (pin "3") (pinfunction "PC14_3") (pintype "bidirectional"))
    )
    (net (code "76") (name "unconnected-(IC3F-PC15-Pad4)") (class "Default")
      (node (ref "IC3") (pin "4") (pinfunction "PC15_4") (pintype "bidirectional"))
    )
    (net (code "77") (name "unconnected-(IC3G-PD0{slash}OSC<=-Pad5)") (class "Default")
      (node (ref "IC3") (pin "5") (pinfunction "PD0/OSC<=_5") (pintype "bidirectional"))
    )
    (net (code "78") (name "unconnected-(IC3G-PD1{slash}OSC=>-Pad6)") (class "Default")
      (node (ref "IC3") (pin "6") (pinfunction "PD1/OSC=>_6") (pintype "bidirectional"))
    )
    (net (code "79") (name "unconnected-(IC3I-BOOT0-Pad44)") (class "Default")
      (node (ref "IC3") (pin "44") (pinfunction "BOOT0_44") (pintype "input"))
    )
    (net (code "80") (name "unconnected-(SG1-1-Pad+)") (class "Default")
      (node (ref "SG1") (pin "+") (pinfunction "1_+") (pintype "passive"))
    )
    (net (code "81") (name "unconnected-(SG1-2-Pad-)") (class "Default")
      (node (ref "SG1") (pin "-") (pinfunction "2_-") (pintype "passive"))
    )
    (net (code "82") (name "unconnected-(SWD-Pad6)") (class "Default")
      (node (ref "SWD") (pin "6") (pinfunction "6_6") (pintype "passive"))
    )
    (net (code "83") (name "unconnected-(X1-Pad2)") (class "Default")
      (node (ref "X1") (pin "2") (pinfunction "2_2") (pintype "input"))
    )
    (net (code "84") (name "unconnected-(X1-Pad3)") (class "Default")
      (node (ref "X1") (pin "3") (pinfunction "3_3") (pintype "input"))
    )
    (net (code "85") (name "unconnected-(X1-Pad4)") (class "Default")
      (node (ref "X1") (pin "4") (pinfunction "4_4") (pintype "input"))
    )
  )
)
